# Schematic_v20.net
KiCad netlist of a schematic drawn in EAGLE
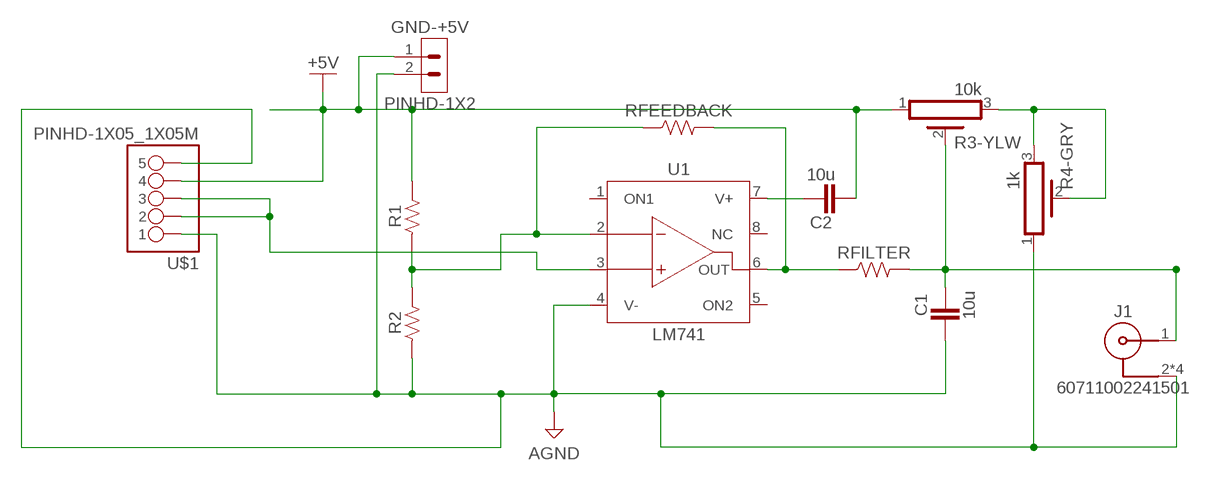
[diagram p0: schematic, sheet 1]

(export (version "E")
  (design (tool "Eeschema 10.0.6"))
  (components
    (comp (ref "C1")
      (value "10u")
      (footprint "eagle-import:CAP-THRU-2.54MM")
      (libsource (lib "eagle-import") (part "CAPACITORCERAMIC-2.54MM"))
    )
    (comp (ref "C2")
      (value "10u")
      (footprint "eagle-import:CAP-THRU-2.54MM")
      (libsource (lib "eagle-import") (part "CAPACITORCERAMIC-2.54MM"))
    )
    (comp (ref "GND-+5V")
      (value "PINHD-1X2")
      (footprint "eagle-import:1X02")
      (libsource (lib "eagle-import") (part "PINHD-1X2"))
    )
    (comp (ref "J1")
      (value "60711002241501")
      (footprint "eagle-import:60711002241501")
      (libsource (lib "eagle-import") (part "60711002241501"))
    )
    (comp (ref "R1")
      (value "1k")
      (footprint "eagle-import:RESAD724W46L381D178B")
      (libsource (lib "eagle-import") (part "R-USAXIAL-7.2MM-PITCH_"))
    )
    (comp (ref "R2")
      (value "1k")
      (footprint "eagle-import:RESAD724W46L381D178B")
      (libsource (lib "eagle-import") (part "R-USAXIAL-7.2MM-PITCH_"))
    )
    (comp (ref "R3-YLW")
      (value "10k")
      (footprint "eagle-import:HA-06-SM065")
      (libsource (lib "eagle-import") (part "POT_HA-06"))
    )
    (comp (ref "R4-GRY")
      (value "1k")
      (footprint "eagle-import:HA-06-SM065")
      (libsource (lib "eagle-import") (part "POT_HA-06"))
    )
    (comp (ref "RFEEDBACK")
      (value "24M")
      (footprint "eagle-import:RESAD724W46L381D178B")
      (libsource (lib "eagle-import") (part "R-USAXIAL-7.2MM-PITCH_"))
    )
    (comp (ref "RFILTER")
      (value "47k")
      (footprint "eagle-import:RESAD724W46L381D178B")
      (libsource (lib "eagle-import") (part "R-USAXIAL-7.2MM-PITCH_"))
    )
    (comp (ref "U$1")
      (value "PINHD-1X05_1X05M")
      (footprint "eagle-import:1X05")
      (libsource (lib "eagle-import") (part "PINHD-1X05_1X05M"))
    )
    (comp (ref "U1")
      (value "LM741")
      (footprint "eagle-import:DIP826W53P254L959H508Q8B")
      (libsource (lib "eagle-import") (part "LM741"))
    )
  )
  (nets
    (net (code "1") (name "+5V") (class "Default")
      (node (ref "C2") (pin "2") (pinfunction "2_2") (pintype "passive"))
      (node (ref "GND-+5V") (pin "1") (pinfunction "1_1") (pintype "passive"))
      (node (ref "R1") (pin "2") (pinfunction "2_2") (pintype "passive"))
      (node (ref "R3-YLW") (pin "1") (pinfunction "P$1_1") (pintype "passive"))
      (node (ref "U$1") (pin "4") (pinfunction "4_4") (pintype "bidirectional"))
    )
    (net (code "2") (name "AGND") (class "Default")
      (node (ref "C1") (pin "2") (pinfunction "2_2") (pintype "passive"))
      (node (ref "GND-+5V") (pin "2") (pinfunction "2_2") (pintype "passive"))
      (node (ref "J1") (pin "2") (pinfunction "2_2") (pintype "passive"))
      (node (ref "J1") (pin "3") (pinfunction "2_3") (pintype "passive"))
      (node (ref "J1") (pin "4") (pinfunction "2_4") (pintype "passive"))
      (node (ref "J1") (pin "5") (pinfunction "2_5") (pintype "passive"))
      (node (ref "R2") (pin "1") (pinfunction "1_1") (pintype "passive"))
      (node (ref "R4-GRY") (pin "1") (pinfunction "P$1_1") (pintype "passive"))
      (node (ref "U$1") (pin "1") (pinfunction "1_1") (pintype "bidirectional"))
      (node (ref "U$1") (pin "5") (pinfunction "5_5") (pintype "bidirectional"))
      (node (ref "U1") (pin "4") (pinfunction "V-_4") (pintype "bidirectional"))
    )
    (net (code "3") (name "Net-(R3-YLW-P$2)") (class "Default")
      (node (ref "C1") (pin "1") (pinfunction "1_1") (pintype "passive"))
      (node (ref "J1") (pin "1") (pinfunction "1_1") (pintype "passive"))
      (node (ref "R3-YLW") (pin "2") (pinfunction "P$2_2") (pintype "passive"))
      (node (ref "RFILTER") (pin "2") (pinfunction "2_2") (pintype "passive"))
    )
    (net (code "4") (name "Net-(R3-YLW-P$3)") (class "Default")
      (node (ref "R3-YLW") (pin "3") (pinfunction "P$3_3") (pintype "passive"))
      (node (ref "R4-GRY") (pin "2") (pinfunction "P$2_2") (pintype "passive"))
      (node (ref "R4-GRY") (pin "3") (pinfunction "P$3_3") (pintype "passive"))
    )
    (net (code "5") (name "Net-(U1-+IN)") (class "Default")
      (node (ref "U$1") (pin "2") (pinfunction "2_2") (pintype "bidirectional"))
      (node (ref "U$1") (pin "3") (pinfunction "3_3") (pintype "bidirectional"))
      (node (ref "U1") (pin "3") (pinfunction "+IN_3") (pintype "input"))
    )
    (net (code "6") (name "Net-(U1--IN)") (class "Default")
      (node (ref "R1") (pin "1") (pinfunction "1_1") (pintype "passive"))
      (node (ref "R2") (pin "2") (pinfunction "2_2") (pintype "passive"))
      (node (ref "RFEEDBACK") (pin "1") (pinfunction "1_1") (pintype "passive"))
      (node (ref "U1") (pin "2") (pinfunction "-IN_2") (pintype "input"))
    )
    (net (code "7") (name "Net-(U1-OUT)") (class "Default")
      (node (ref "RFEEDBACK") (pin "2") (pinfunction "2_2") (pintype "passive"))
      (node (ref "RFILTER") (pin "1") (pinfunction "1_1") (pintype "passive"))
      (node (ref "U1") (pin "6") (pinfunction "OUT_6") (pintype "output"))
    )
    (net (code "8") (name "Net-(U1-V+)") (class "Default")
      (node (ref "C2") (pin "1") (pinfunction "1_1") (pintype "passive"))
      (node (ref "U1") (pin "7") (pinfunction "V+_7") (pintype "bidirectional"))
    )
    (net (code "9") (name "unconnected-(U1-NC-Pad8)") (class "Default")
      (node (ref "U1") (pin "8") (pinfunction "NC_8") (pintype "passive"))
    )
    (net (code "10") (name "unconnected-(U1-ON1-Pad1)") (class "Default")
      (node (ref "U1") (pin "1") (pinfunction "ON1_1") (pintype "passive"))
    )
    (net (code "11") (name "unconnected-(U1-ON2-Pad5)") (class "Default")
      (node (ref "U1") (pin "5") (pinfunction "ON2_5") (pintype "passive"))
    )
  )
)
